# Drive.net
KiCad netlist of a schematic drawn in Altium Designer
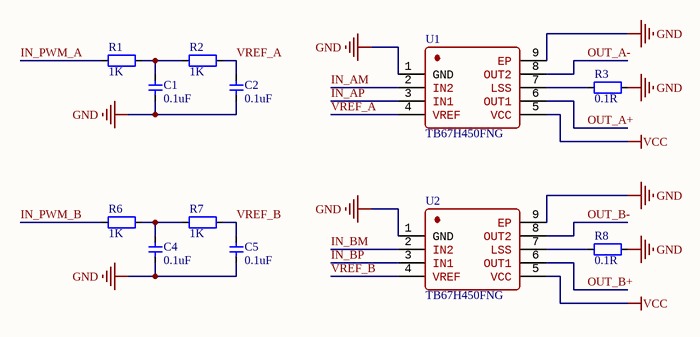
[diagram p0: Drive.SchDoc]

(export (version "E")
  (design (tool "Eeschema 10.0.6"))
  (components
    (comp (ref "C1")
      (value "0.1uF")
      (footprint "CAP_0402")
      (description "Capacitor")
      (libsource (lib "MyPcbLib") (part "电容-0402"))
    )
    (comp (ref "C2")
      (value "0.1uF")
      (footprint "CAP_0402")
      (description "Capacitor")
      (libsource (lib "MyPcbLib") (part "电容-0402"))
    )
    (comp (ref "C4")
      (value "0.1uF")
      (footprint "CAP_0402")
      (description "Capacitor")
      (libsource (lib "MyPcbLib") (part "电容-0402"))
    )
    (comp (ref "C5")
      (value "0.1uF")
      (footprint "CAP_0402")
      (description "Capacitor")
      (libsource (lib "MyPcbLib") (part "电容-0402"))
    )
    (comp (ref "R1")
      (value "1K")
      (footprint "RES_0402")
      (description "Resistor")
      (libsource (lib "MyPcbLib") (part "电阻-0402"))
    )
    (comp (ref "R2")
      (value "1K")
      (footprint "RES_0402")
      (description "Resistor")
      (libsource (lib "MyPcbLib") (part "电阻-0402"))
    )
    (comp (ref "R3")
      (value "0.1R")
      (footprint "1206-RES")
      (description "Resistor")
      (libsource (lib "MyPcbLib") (part "电阻-1206"))
    )
    (comp (ref "R6")
      (value "1K")
      (footprint "RES_0402")
      (description "Resistor")
      (libsource (lib "MyPcbLib") (part "电阻-0402"))
    )
    (comp (ref "R7")
      (value "1K")
      (footprint "RES_0402")
      (description "Resistor")
      (libsource (lib "MyPcbLib") (part "电阻-0402"))
    )
    (comp (ref "R8")
      (value "0.1R")
      (footprint "1206-RES")
      (description "Resistor")
      (libsource (lib "MyPcbLib") (part "电阻-1206"))
    )
    (comp (ref "U1")
      (value "TB67H450FNG")
      (footprint "SO-8-PAD")
      (description "PWM Chopper Type DC Brushed Motor Driver")
      (libsource (lib "MyPcbLib") (part "TB67H450FNG"))
    )
    (comp (ref "U2")
      (value "TB67H450FNG")
      (footprint "SO-8-PAD")
      (description "PWM Chopper Type DC Brushed Motor Driver")
      (libsource (lib "MyPcbLib") (part "TB67H450FNG"))
    )
  )
  (nets
    (net (code "1") (name "/IN_AM") (class "Default")
      (node (ref "U1") (pin "2") (pinfunction "IN2_2") (pintype "passive"))
    )
    (net (code "2") (name "/IN_AP") (class "Default")
      (node (ref "U1") (pin "3") (pinfunction "IN1_3") (pintype "passive"))
    )
    (net (code "3") (name "/IN_BM") (class "Default")
      (node (ref "U2") (pin "2") (pinfunction "IN2_2") (pintype "passive"))
    )
    (net (code "4") (name "/IN_BP") (class "Default")
      (node (ref "U2") (pin "3") (pinfunction "IN1_3") (pintype "passive"))
    )
    (net (code "5") (name "/IN_PWM_A") (class "Default")
      (node (ref "R1") (pin "1") (pinfunction "1_1") (pintype "passive"))
    )
    (net (code "6") (name "/IN_PWM_B") (class "Default")
      (node (ref "R6") (pin "1") (pinfunction "1_1") (pintype "passive"))
    )
    (net (code "7") (name "/OUT_A+") (class "Default")
      (node (ref "U1") (pin "6") (pinfunction "OUT1_6") (pintype "passive"))
    )
    (net (code "8") (name "/OUT_A-") (class "Default")
      (node (ref "U1") (pin "8") (pinfunction "OUT2_8") (pintype "passive"))
    )
    (net (code "9") (name "/OUT_B+") (class "Default")
      (node (ref "U2") (pin "6") (pinfunction "OUT1_6") (pintype "passive"))
    )
    (net (code "10") (name "/OUT_B-") (class "Default")
      (node (ref "U2") (pin "8") (pinfunction "OUT2_8") (pintype "passive"))
    )
    (net (code "11") (name "/VREF_A") (class "Default")
      (node (ref "C2") (pin "2") (pinfunction "2_2") (pintype "passive"))
      (node (ref "R2") (pin "2") (pinfunction "2_2") (pintype "passive"))
      (node (ref "U1") (pin "4") (pinfunction "VREF_4") (pintype "passive"))
    )
    (net (code "12") (name "/VREF_B") (class "Default")
      (node (ref "C5") (pin "2") (pinfunction "2_2") (pintype "passive"))
      (node (ref "R7") (pin "2") (pinfunction "2_2") (pintype "passive"))
      (node (ref "U2") (pin "4") (pinfunction "VREF_4") (pintype "passive"))
    )
    (net (code "13") (name "GND") (class "Default")
      (node (ref "C1") (pin "1") (pinfunction "1_1") (pintype "passive"))
      (node (ref "C2") (pin "1") (pinfunction "1_1") (pintype "passive"))
      (node (ref "C4") (pin "1") (pinfunction "1_1") (pintype "passive"))
      (node (ref "C5") (pin "1") (pinfunction "1_1") (pintype "passive"))
      (node (ref "R3") (pin "2") (pinfunction "2_2") (pintype "passive"))
      (node (ref "R8") (pin "2") (pinfunction "2_2") (pintype "passive"))
      (node (ref "U1") (pin "1") (pinfunction "GND_1") (pintype "passive"))
      (node (ref "U1") (pin "9") (pinfunction "EP_9") (pintype "passive"))
      (node (ref "U2") (pin "1") (pinfunction "GND_1") (pintype "passive"))
      (node (ref "U2") (pin "9") (pinfunction "EP_9") (pintype "passive"))
    )
    (net (code "14") (name "Net-(C1-Pad2)") (class "Default")
      (node (ref "C1") (pin "2") (pinfunction "2_2") (pintype "passive"))
      (node (ref "R1") (pin "2") (pinfunction "2_2") (pintype "passive"))
      (node (ref "R2") (pin "1") (pinfunction "1_1") (pintype "passive"))
    )
    (net (code "15") (name "Net-(C4-Pad2)") (class "Default")
      (node (ref "C4") (pin "2") (pinfunction "2_2") (pintype "passive"))
      (node (ref "R6") (pin "2") (pinfunction "2_2") (pintype "passive"))
      (node (ref "R7") (pin "1") (pinfunction "1_1") (pintype "passive"))
    )
    (net (code "16") (name "Net-(U1-LSS)") (class "Default")
      (node (ref "R3") (pin "1") (pinfunction "1_1") (pintype "passive"))
      (node (ref "U1") (pin "7") (pinfunction "LSS_7") (pintype "passive"))
    )
    (net (code "17") (name "Net-(U2-LSS)") (class "Default")
      (node (ref "R8") (pin "1") (pinfunction "1_1") (pintype "passive"))
      (node (ref "U2") (pin "7") (pinfunction "LSS_7") (pintype "passive"))
    )
    (net (code "18") (name "VCC") (class "Default")
      (node (ref "U1") (pin "5") (pinfunction "VCC_5") (pintype "passive"))
      (node (ref "U2") (pin "5") (pinfunction "VCC_5") (pintype "passive"))
    )
  )
)
